# Yitran_IT900_Hutschiene_1_3.net
KiCad netlist of a schematic drawn in EAGLE
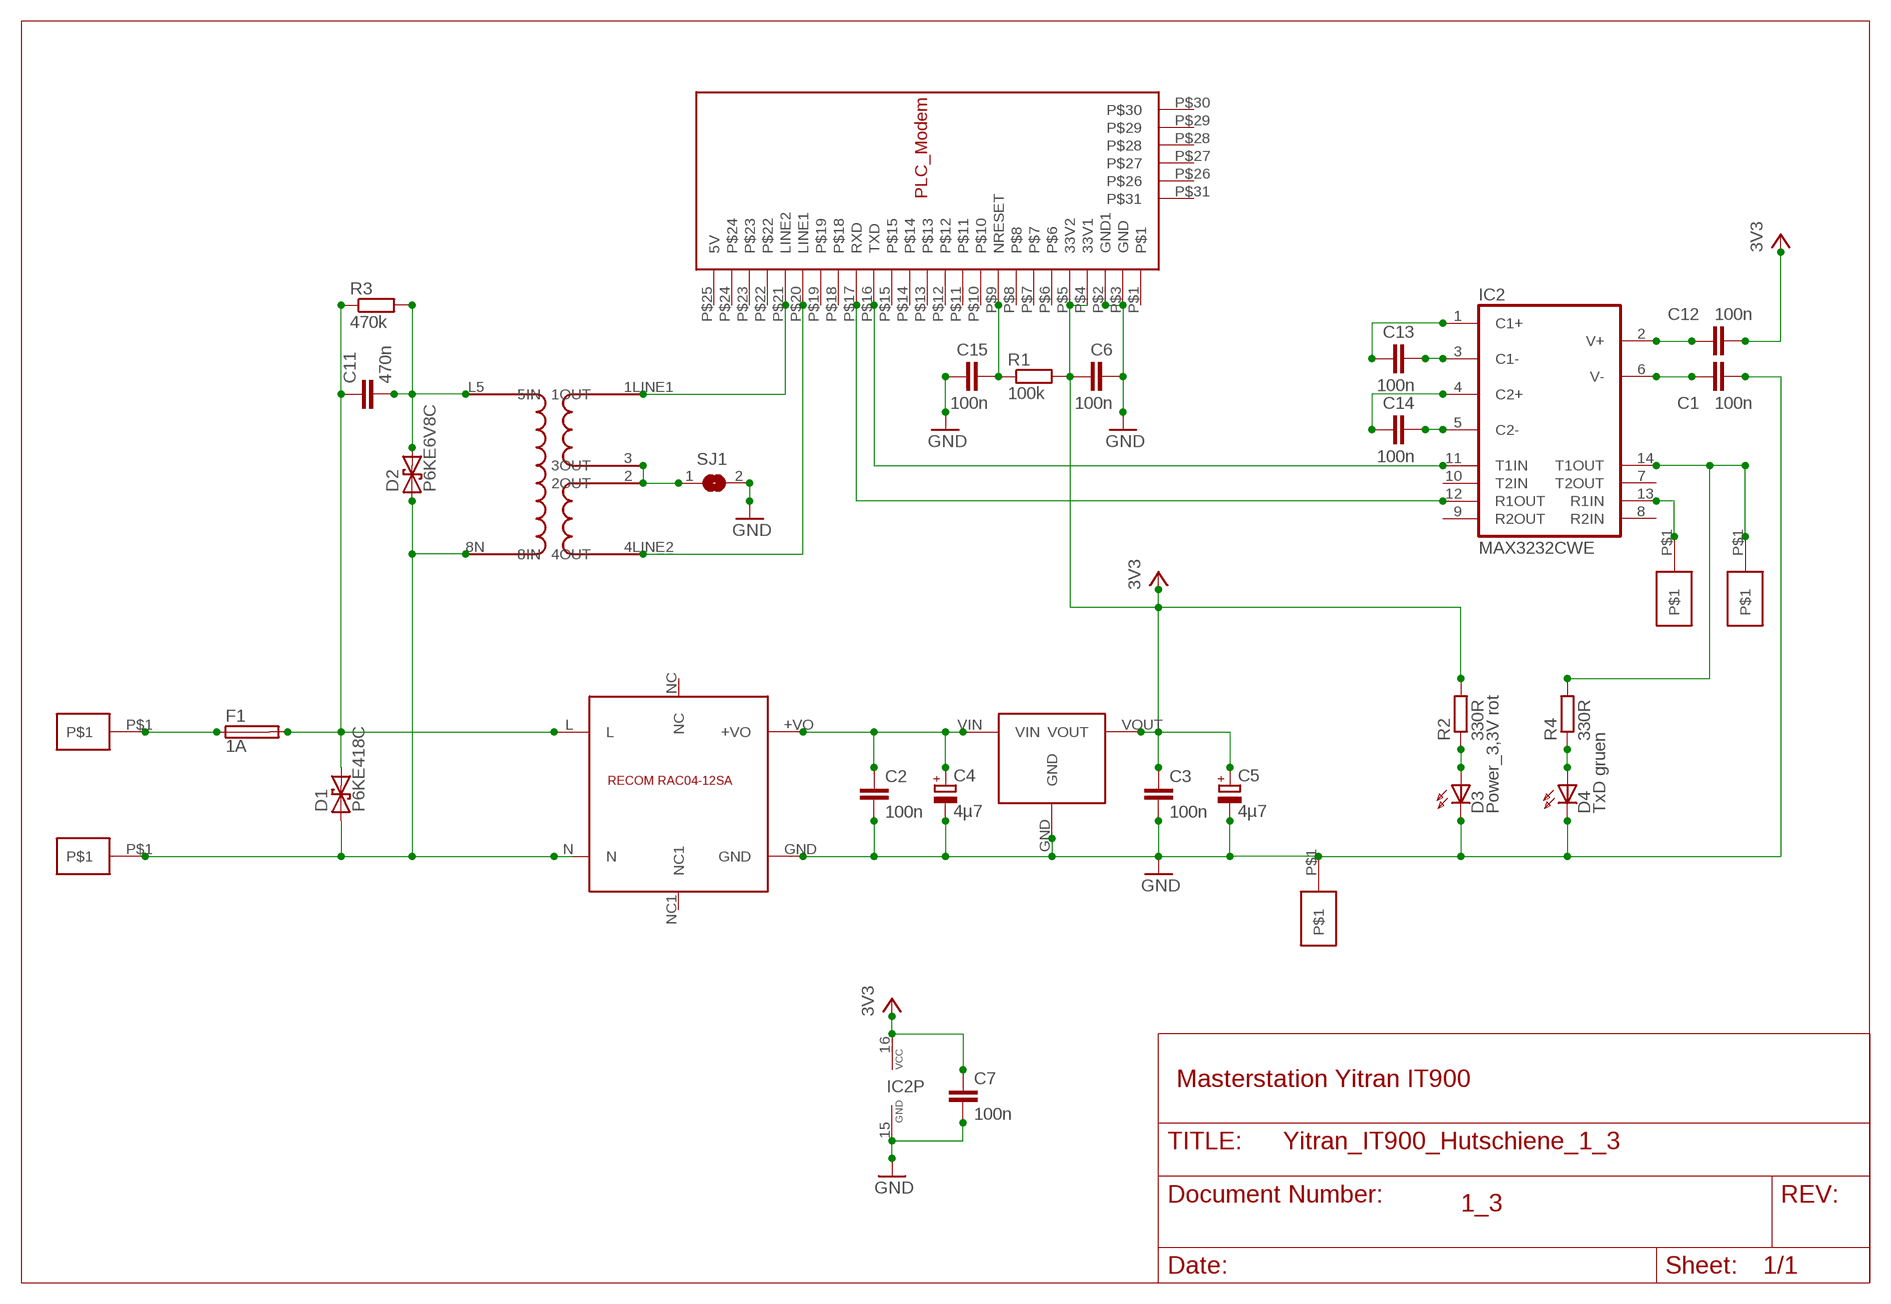
[diagram p0: schematic, sheet 1]

(export (version "E")
  (design (tool "Eeschema 10.0.6"))
  (components
    (comp (ref "C1")
      (value "100n")
      (footprint "eagle-import:C1206K")
      (libsource (lib "eagle-import") (part "C-EUC1206K"))
    )
    (comp (ref "C2")
      (value "100n")
      (footprint "eagle-import:C1206K")
      (libsource (lib "eagle-import") (part "C-EUC1206K"))
    )
    (comp (ref "C3")
      (value "100n")
      (footprint "eagle-import:C1206K")
      (libsource (lib "eagle-import") (part "C-EUC1206K"))
    )
    (comp (ref "C4")
      (value "4µ7")
      (footprint "eagle-import:E2,5-5")
      (libsource (lib "eagle-import") (part "CPOL-EUE2.5-5"))
    )
    (comp (ref "C5")
      (value "4µ7")
      (footprint "eagle-import:E2,5-5")
      (libsource (lib "eagle-import") (part "CPOL-EUE2.5-5"))
    )
    (comp (ref "C6")
      (value "100n")
      (footprint "eagle-import:C1206K")
      (libsource (lib "eagle-import") (part "C-EUC1206K"))
    )
    (comp (ref "C7")
      (value "100n")
      (footprint "eagle-import:C1206K")
      (libsource (lib "eagle-import") (part "C-EUC1206K"))
    )
    (comp (ref "C11")
      (value "470n")
      (footprint "eagle-import:C150-091X182")
      (libsource (lib "eagle-import") (part "C-EU150-091X182"))
    )
    (comp (ref "C12")
      (value "100n")
      (footprint "eagle-import:C1206K")
      (libsource (lib "eagle-import") (part "C-EUC1206K"))
    )
    (comp (ref "C13")
      (value "100n")
      (footprint "eagle-import:C1206K")
      (libsource (lib "eagle-import") (part "C-EUC1206K"))
    )
    (comp (ref "C14")
      (value "100n")
      (footprint "eagle-import:C1206K")
      (libsource (lib "eagle-import") (part "C-EUC1206K"))
    )
    (comp (ref "C15")
      (value "100n")
      (footprint "eagle-import:C1206K")
      (libsource (lib "eagle-import") (part "C-EUC1206K"))
    )
    (comp (ref "D1")
      (value "P6KE418C")
      (footprint "eagle-import:CB417-15")
      (libsource (lib "eagle-import") (part "P6KEXXC"))
    )
    (comp (ref "D2")
      (value "P6KE6V8C")
      (footprint "eagle-import:CB417-15")
      (libsource (lib "eagle-import") (part "P6KEXXC"))
    )
    (comp (ref "D3")
      (value "Power_3,3V rot")
      (footprint "eagle-import:HLMP6")
      (fields (field (name "MF") "AGILENT TECHNOLOGIES") (field (name "MPN") "HLMP-6500"))
      (libsource (lib "eagle-import") (part "HLMP6"))
    )
    (comp (ref "D4")
      (value "TxD gruen")
      (footprint "eagle-import:HLMP6")
      (fields (field (name "MF") "AGILENT TECHNOLOGIES") (field (name "MPN") "HLMP-6500"))
      (libsource (lib "eagle-import") (part "HLMP6"))
    )
    (comp (ref "F1")
      (value "1A")
      (footprint "eagle-import:TR5")
      (libsource (lib "eagle-import") (part "TR5"))
    )
    (comp (ref "GND")
      (value "PN4")
      (footprint "eagle-import:PIN2")
      (libsource (lib "eagle-import") (part "PN4"))
    )
    (comp (ref "IC2")
      (value "MAX3232CWE")
      (footprint "eagle-import:SO16L")
      (fields (field (name "MF") "MAXIM") (field (name "MPN") "MAX3232CWE+"))
      (libsource (lib "eagle-import") (part "MAX3232WEC"))
    )
    (comp (ref "PL1")
      (value "PN4")
      (footprint "eagle-import:PIN2")
      (libsource (lib "eagle-import") (part "PN4"))
    )
    (comp (ref "PL2")
      (value "PN4")
      (footprint "eagle-import:PIN2")
      (libsource (lib "eagle-import") (part "PN4"))
    )
    (comp (ref "R1")
      (value "100k")
      (footprint "eagle-import:M1406")
      (libsource (lib "eagle-import") (part "R-EU_M1406"))
    )
    (comp (ref "R2")
      (value "330R")
      (footprint "eagle-import:R1206")
      (libsource (lib "eagle-import") (part "R-EU_R1206"))
    )
    (comp (ref "R3")
      (value "470k")
      (footprint "eagle-import:0309_10")
      (libsource (lib "eagle-import") (part "R-EU_0309/10"))
    )
    (comp (ref "R4")
      (value "330R")
      (footprint "eagle-import:R1206")
      (libsource (lib "eagle-import") (part "R-EU_R1206"))
    )
    (comp (ref "RXD")
      (value "PN4")
      (footprint "eagle-import:PIN2")
      (libsource (lib "eagle-import") (part "PN4"))
    )
    (comp (ref "SJ1")
      (value "SJW")
      (footprint "eagle-import:SJW")
      (libsource (lib "eagle-import") (part "SJW"))
    )
    (comp (ref "TXD")
      (value "PN4")
      (footprint "eagle-import:PIN2")
      (libsource (lib "eagle-import") (part "PN4"))
    )
    (comp (ref "U$1")
      (value "RECOM_783_3")
      (footprint "eagle-import:RECOM785X")
      (libsource (lib "eagle-import") (part "RECOM_785_05"))
    )
    (comp (ref "U$3")
      (value "MODEMSTECKER")
      (footprint "eagle-import:MODEM_FUSS")
      (libsource (lib "eagle-import") (part "MODEMSTECKER"))
    )
    (comp (ref "U$9")
      (value "RECOM_RAC04_12SA")
      (footprint "eagle-import:RAC04_12SA")
      (libsource (lib "eagle-import") (part "RECOM_RAC04_12SA"))
    )
    (comp (ref "U$10")
      (value "PLC_UEBERTRAGER_V2")
      (footprint "eagle-import:PLC-UEBERTRAGER_V2")
      (libsource (lib "eagle-import") (part "PLC_UEBERTRAGER_V2"))
    )
  )
  (nets
    (net (code "1") (name "3V3") (class "Default")
      (node (ref "C12") (pin "2") (pinfunction "2_2") (pintype "passive"))
      (node (ref "C3") (pin "1") (pinfunction "1_1") (pintype "passive"))
      (node (ref "C5") (pin "+") (pinfunction "+_+") (pintype "passive"))
      (node (ref "C6") (pin "1") (pinfunction "1_1") (pintype "passive"))
      (node (ref "C7") (pin "1") (pinfunction "1_1") (pintype "passive"))
      (node (ref "IC2") (pin "16") (pinfunction "VCC_16") (pintype "power_in"))
      (node (ref "R1") (pin "2") (pinfunction "2_2") (pintype "passive"))
      (node (ref "R2") (pin "2") (pinfunction "2_2") (pintype "passive"))
      (node (ref "U$1") (pin "VOUT") (pinfunction "VOUT_VOUT") (pintype "bidirectional"))
      (node (ref "U$3") (pin "P$4") (pinfunction "33V1_P$4") (pintype "bidirectional"))
      (node (ref "U$3") (pin "P$5") (pinfunction "33V2_P$5") (pintype "bidirectional"))
    )
    (net (code "2") (name "GND") (class "Default")
      (node (ref "C1") (pin "2") (pinfunction "2_2") (pintype "passive"))
      (node (ref "C15") (pin "1") (pinfunction "1_1") (pintype "passive"))
      (node (ref "C2") (pin "2") (pinfunction "2_2") (pintype "passive"))
      (node (ref "C3") (pin "2") (pinfunction "2_2") (pintype "passive"))
      (node (ref "C4") (pin "-") (pinfunction "-_-") (pintype "passive"))
      (node (ref "C5") (pin "-") (pinfunction "-_-") (pintype "passive"))
      (node (ref "C6") (pin "2") (pinfunction "2_2") (pintype "passive"))
      (node (ref "C7") (pin "2") (pinfunction "2_2") (pintype "passive"))
      (node (ref "D3") (pin "K") (pinfunction "K_K") (pintype "passive"))
      (node (ref "D4") (pin "K") (pinfunction "K_K") (pintype "passive"))
      (node (ref "GND") (pin "P$1") (pinfunction "P$1_P$1") (pintype "bidirectional"))
      (node (ref "IC2") (pin "15") (pinfunction "GND_15") (pintype "power_in"))
      (node (ref "SJ1") (pin "2") (pinfunction "2_2") (pintype "passive"))
      (node (ref "U$1") (pin "GND") (pinfunction "GND_GND") (pintype "bidirectional"))
      (node (ref "U$3") (pin "P$2") (pinfunction "GND1_P$2") (pintype "bidirectional"))
      (node (ref "U$3") (pin "P$3") (pinfunction "GND_P$3") (pintype "bidirectional"))
      (node (ref "U$9") (pin "GND") (pinfunction "GND_GND") (pintype "bidirectional"))
    )
    (net (code "3") (name "Net-(C2-Pad1)") (class "Default")
      (node (ref "C2") (pin "1") (pinfunction "1_1") (pintype "passive"))
      (node (ref "C4") (pin "+") (pinfunction "+_+") (pintype "passive"))
      (node (ref "U$1") (pin "VIN") (pinfunction "VIN_VIN") (pintype "bidirectional"))
      (node (ref "U$9") (pin "+VO") (pinfunction "+VO_+VO") (pintype "bidirectional"))
    )
    (net (code "4") (name "Net-(D1-1)") (class "Default")
      (node (ref "D1") (pin "A") (pinfunction "1_A") (pintype "passive"))
      (node (ref "D2") (pin "A") (pinfunction "1_A") (pintype "passive"))
      (node (ref "PL2") (pin "P$1") (pinfunction "P$1_P$1") (pintype "bidirectional"))
      (node (ref "U$10") (pin "8N") (pinfunction "8IN_8N") (pintype "input"))
      (node (ref "U$9") (pin "N") (pinfunction "N_N") (pintype "bidirectional"))
    )
    (net (code "5") (name "Net-(D1-2)") (class "Default")
      (node (ref "C11") (pin "1") (pinfunction "1_1") (pintype "passive"))
      (node (ref "D1") (pin "C") (pinfunction "2_C") (pintype "passive"))
      (node (ref "F1") (pin "2") (pinfunction "2_2") (pintype "passive"))
      (node (ref "R3") (pin "1") (pinfunction "1_1") (pintype "passive"))
      (node (ref "U$9") (pin "L") (pinfunction "L_L") (pintype "bidirectional"))
    )
    (net (code "6") (name "Net-(D2-2)") (class "Default")
      (node (ref "C11") (pin "2") (pinfunction "2_2") (pintype "passive"))
      (node (ref "D2") (pin "C") (pinfunction "2_C") (pintype "passive"))
      (node (ref "R3") (pin "2") (pinfunction "2_2") (pintype "passive"))
      (node (ref "U$10") (pin "L5") (pinfunction "5IN_L5") (pintype "input"))
    )
    (net (code "7") (name "Net-(D3-PadA)") (class "Default")
      (node (ref "D3") (pin "A") (pinfunction "A_A") (pintype "passive"))
      (node (ref "R2") (pin "1") (pinfunction "1_1") (pintype "passive"))
    )
    (net (code "8") (name "Net-(D4-PadA)") (class "Default")
      (node (ref "D4") (pin "A") (pinfunction "A_A") (pintype "passive"))
      (node (ref "R4") (pin "1") (pinfunction "1_1") (pintype "passive"))
    )
    (net (code "9") (name "Net-(F1-Pad1)") (class "Default")
      (node (ref "F1") (pin "1") (pinfunction "1_1") (pintype "passive"))
      (node (ref "PL1") (pin "P$1") (pinfunction "P$1_P$1") (pintype "bidirectional"))
    )
    (net (code "10") (name "Net-(IC2A-C1+)") (class "Default")
      (node (ref "C13") (pin "1") (pinfunction "1_1") (pintype "passive"))
      (node (ref "IC2") (pin "1") (pinfunction "C1+_1") (pintype "bidirectional"))
    )
    (net (code "11") (name "Net-(IC2A-C1-)") (class "Default")
      (node (ref "C13") (pin "2") (pinfunction "2_2") (pintype "passive"))
      (node (ref "IC2") (pin "3") (pinfunction "C1-_3") (pintype "bidirectional"))
    )
    (net (code "12") (name "Net-(IC2A-C2+)") (class "Default")
      (node (ref "C14") (pin "1") (pinfunction "1_1") (pintype "passive"))
      (node (ref "IC2") (pin "4") (pinfunction "C2+_4") (pintype "bidirectional"))
    )
    (net (code "13") (name "Net-(IC2A-C2-)") (class "Default")
      (node (ref "C14") (pin "2") (pinfunction "2_2") (pintype "passive"))
      (node (ref "IC2") (pin "5") (pinfunction "C2-_5") (pintype "bidirectional"))
    )
    (net (code "14") (name "Net-(IC2A-R1IN)") (class "Default")
      (node (ref "IC2") (pin "13") (pinfunction "R1IN_13") (pintype "input"))
      (node (ref "RXD") (pin "P$1") (pinfunction "P$1_P$1") (pintype "bidirectional"))
    )
    (net (code "15") (name "Net-(IC2A-R1OUT)") (class "Default")
      (node (ref "IC2") (pin "12") (pinfunction "R1OUT_12") (pintype "output"))
      (node (ref "U$3") (pin "P$17") (pinfunction "RXD_P$17") (pintype "bidirectional"))
    )
    (net (code "16") (name "Net-(IC2A-T1IN)") (class "Default")
      (node (ref "IC2") (pin "11") (pinfunction "T1IN_11") (pintype "input"))
      (node (ref "U$3") (pin "P$16") (pinfunction "TXD_P$16") (pintype "bidirectional"))
    )
    (net (code "17") (name "Net-(IC2A-T1OUT)") (class "Default")
      (node (ref "IC2") (pin "14") (pinfunction "T1OUT_14") (pintype "output"))
      (node (ref "R4") (pin "2") (pinfunction "2_2") (pintype "passive"))
      (node (ref "TXD") (pin "P$1") (pinfunction "P$1_P$1") (pintype "bidirectional"))
    )
    (net (code "18") (name "Net-(IC2A-V+)") (class "Default")
      (node (ref "C12") (pin "1") (pinfunction "1_1") (pintype "passive"))
      (node (ref "IC2") (pin "2") (pinfunction "V+_2") (pintype "bidirectional"))
    )
    (net (code "19") (name "Net-(IC2A-V-)") (class "Default")
      (node (ref "C1") (pin "1") (pinfunction "1_1") (pintype "passive"))
      (node (ref "IC2") (pin "6") (pinfunction "V-_6") (pintype "bidirectional"))
    )
    (net (code "20") (name "Net-(U$3-NRESET)") (class "Default")
      (node (ref "C15") (pin "2") (pinfunction "2_2") (pintype "passive"))
      (node (ref "R1") (pin "1") (pinfunction "1_1") (pintype "passive"))
      (node (ref "U$3") (pin "P$9") (pinfunction "NRESET_P$9") (pintype "bidirectional"))
    )
    (net (code "21") (name "Net-(U$10-1OUT)") (class "Default")
      (node (ref "U$10") (pin "1LINE1") (pinfunction "1OUT_1LINE1") (pintype "output"))
      (node (ref "U$3") (pin "P$21") (pinfunction "LINE2_P$21") (pintype "bidirectional"))
    )
    (net (code "22") (name "Net-(U$10-2OUT)") (class "Default")
      (node (ref "SJ1") (pin "1") (pinfunction "1_1") (pintype "passive"))
      (node (ref "U$10") (pin "2") (pinfunction "2OUT_2") (pintype "output"))
      (node (ref "U$10") (pin "3") (pinfunction "3OUT_3") (pintype "output"))
    )
    (net (code "23") (name "Net-(U$10-4OUT)") (class "Default")
      (node (ref "U$10") (pin "4LINE2") (pinfunction "4OUT_4LINE2") (pintype "output"))
      (node (ref "U$3") (pin "P$20") (pinfunction "LINE1_P$20") (pintype "bidirectional"))
    )
    (net (code "24") (name "unconnected-(IC2A-R2IN-Pad8)") (class "Default")
      (node (ref "IC2") (pin "8") (pinfunction "R2IN_8") (pintype "input"))
    )
    (net (code "25") (name "unconnected-(IC2A-R2OUT-Pad9)") (class "Default")
      (node (ref "IC2") (pin "9") (pinfunction "R2OUT_9") (pintype "output"))
    )
    (net (code "26") (name "unconnected-(IC2A-T2IN-Pad10)") (class "Default")
      (node (ref "IC2") (pin "10") (pinfunction "T2IN_10") (pintype "input"))
    )
    (net (code "27") (name "unconnected-(IC2A-T2OUT-Pad7)") (class "Default")
      (node (ref "IC2") (pin "7") (pinfunction "T2OUT_7") (pintype "output"))
    )
    (net (code "28") (name "unconnected-(U$3-5V-PadP$25)") (class "Default")
      (node (ref "U$3") (pin "P$25") (pinfunction "5V_P$25") (pintype "bidirectional"))
    )
    (net (code "29") (name "unconnected-(U$3-PadP$1)") (class "Default")
      (node (ref "U$3") (pin "P$1") (pinfunction "P$1_P$1") (pintype "bidirectional"))
    )
    (net (code "30") (name "unconnected-(U$3-PadP$6)") (class "Default")
      (node (ref "U$3") (pin "P$6") (pinfunction "P$6_P$6") (pintype "bidirectional"))
    )
    (net (code "31") (name "unconnected-(U$3-PadP$7)") (class "Default")
      (node (ref "U$3") (pin "P$7") (pinfunction "P$7_P$7") (pintype "bidirectional"))
    )
    (net (code "32") (name "unconnected-(U$3-PadP$8)") (class "Default")
      (node (ref "U$3") (pin "P$8") (pinfunction "P$8_P$8") (pintype "bidirectional"))
    )
    (net (code "33") (name "unconnected-(U$3-PadP$10)") (class "Default")
      (node (ref "U$3") (pin "P$10") (pinfunction "P$10_P$10") (pintype "bidirectional"))
    )
    (net (code "34") (name "unconnected-(U$3-PadP$11)") (class "Default")
      (node (ref "U$3") (pin "P$11") (pinfunction "P$11_P$11") (pintype "bidirectional"))
    )
    (net (code "35") (name "unconnected-(U$3-PadP$12)") (class "Default")
      (node (ref "U$3") (pin "P$12") (pinfunction "P$12_P$12") (pintype "bidirectional"))
    )
    (net (code "36") (name "unconnected-(U$3-PadP$13)") (class "Default")
      (node (ref "U$3") (pin "P$13") (pinfunction "P$13_P$13") (pintype "bidirectional"))
    )
    (net (code "37") (name "unconnected-(U$3-PadP$14)") (class "Default")
      (node (ref "U$3") (pin "P$14") (pinfunction "P$14_P$14") (pintype "bidirectional"))
    )
    (net (code "38") (name "unconnected-(U$3-PadP$15)") (class "Default")
      (node (ref "U$3") (pin "P$15") (pinfunction "P$15_P$15") (pintype "bidirectional"))
    )
    (net (code "39") (name "unconnected-(U$3-PadP$18)") (class "Default")
      (node (ref "U$3") (pin "P$18") (pinfunction "P$18_P$18") (pintype "bidirectional"))
    )
    (net (code "40") (name "unconnected-(U$3-PadP$19)") (class "Default")
      (node (ref "U$3") (pin "P$19") (pinfunction "P$19_P$19") (pintype "bidirectional"))
    )
    (net (code "41") (name "unconnected-(U$3-PadP$22)") (class "Default")
      (node (ref "U$3") (pin "P$22") (pinfunction "P$22_P$22") (pintype "bidirectional"))
    )
    (net (code "42") (name "unconnected-(U$3-PadP$23)") (class "Default")
      (node (ref "U$3") (pin "P$23") (pinfunction "P$23_P$23") (pintype "bidirectional"))
    )
    (net (code "43") (name "unconnected-(U$3-PadP$24)") (class "Default")
      (node (ref "U$3") (pin "P$24") (pinfunction "P$24_P$24") (pintype "bidirectional"))
    )
    (net (code "44") (name "unconnected-(U$3-PadP$26)") (class "Default")
      (node (ref "U$3") (pin "P$26") (pinfunction "P$26_P$26") (pintype "bidirectional"))
    )
    (net (code "45") (name "unconnected-(U$3-PadP$27)") (class "Default")
      (node (ref "U$3") (pin "P$27") (pinfunction "P$27_P$27") (pintype "bidirectional"))
    )
    (net (code "46") (name "unconnected-(U$3-PadP$28)") (class "Default")
      (node (ref "U$3") (pin "P$28") (pinfunction "P$28_P$28") (pintype "bidirectional"))
    )
    (net (code "47") (name "unconnected-(U$3-PadP$29)") (class "Default")
      (node (ref "U$3") (pin "P$29") (pinfunction "P$29_P$29") (pintype "bidirectional"))
    )
    (net (code "48") (name "unconnected-(U$3-PadP$30)") (class "Default")
      (node (ref "U$3") (pin "P$30") (pinfunction "P$30_P$30") (pintype "bidirectional"))
    )
    (net (code "49") (name "unconnected-(U$3-PadP$31)") (class "Default")
      (node (ref "U$3") (pin "P$31") (pinfunction "P$31_P$31") (pintype "bidirectional"))
    )
    (net (code "50") (name "unconnected-(U$9-PadNC)") (class "Default")
      (node (ref "U$9") (pin "NC") (pinfunction "NC_NC") (pintype "bidirectional"))
    )
    (net (code "51") (name "unconnected-(U$9-PadNC1)") (class "Default")
      (node (ref "U$9") (pin "NC1") (pinfunction "NC1_NC1") (pintype "bidirectional"))
    )
  )
)
